# sensormoisture.net
KiCad netlist of a schematic drawn in EAGLE
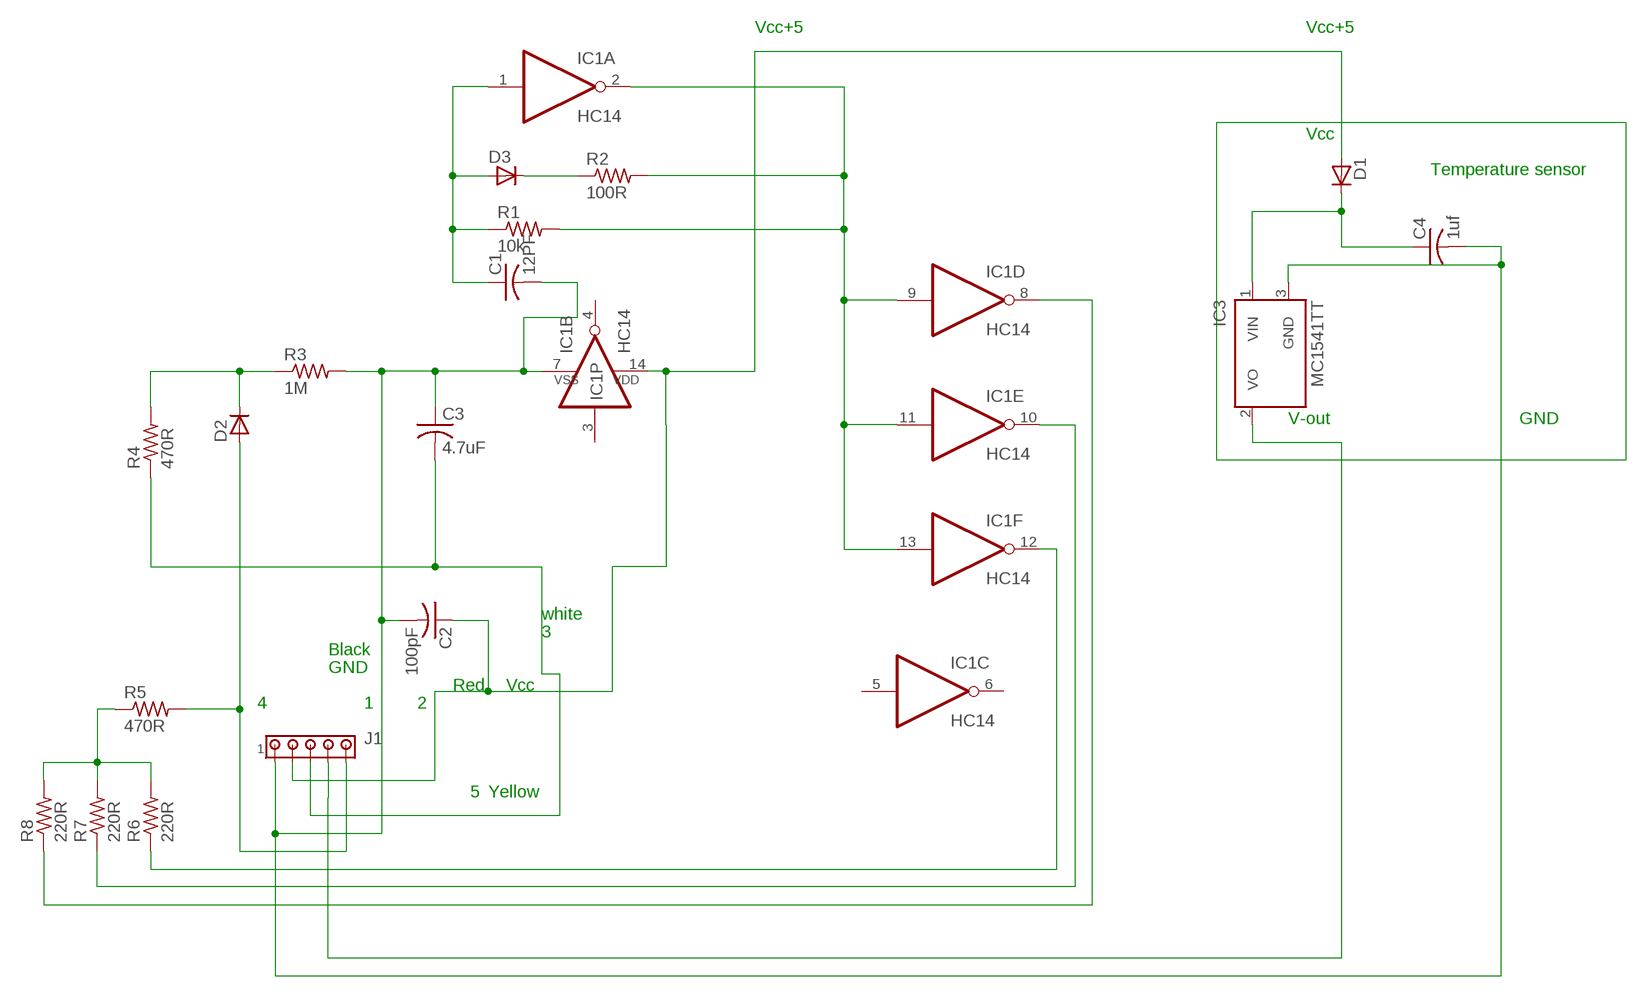
[diagram p0: schematic, sheet 1]

(export (version "E")
  (design (tool "Eeschema 10.0.6"))
  (components
    (comp (ref "C1")
      (value "12PF")
      (footprint "eagle-import:C0805")
      (libsource (lib "eagle-import") (part "C-USC0805"))
    )
    (comp (ref "C2")
      (value "100pF")
      (footprint "eagle-import:C1206K")
      (libsource (lib "eagle-import") (part "C-USC1206K"))
    )
    (comp (ref "C3")
      (value "4.7uF")
      (footprint "eagle-import:C1206")
      (libsource (lib "eagle-import") (part "C-USC1206"))
    )
    (comp (ref "C4")
      (value "1uf")
      (footprint "eagle-import:C1206K")
      (libsource (lib "eagle-import") (part "C-USC1206K"))
    )
    (comp (ref "D1")
      (value "D-MLL-34")
      (footprint "eagle-import:MELF-MLL34")
      (libsource (lib "eagle-import") (part "D-MLL-34"))
    )
    (comp (ref "D2")
      (value "D-MLL-34")
      (footprint "eagle-import:MELF-MLL34")
      (libsource (lib "eagle-import") (part "D-MLL-34"))
    )
    (comp (ref "D3")
      (value "D-MLL-34")
      (footprint "eagle-import:MELF-MLL34")
      (libsource (lib "eagle-import") (part "D-MLL-34"))
    )
    (comp (ref "IC1")
      (value "HC14")
      (footprint "eagle-import:SO14")
      (libsource (lib "eagle-import") (part "4584D"))
    )
    (comp (ref "IC3")
      (value "MC1541TT")
      (footprint "eagle-import:SOT23")
      (libsource (lib "eagle-import") (part "MC15TT41"))
    )
    (comp (ref "J1")
      (value "MTA05-100")
      (footprint "eagle-import:10X05MTA")
      (libsource (lib "eagle-import") (part "MTA05-100"))
    )
    (comp (ref "R1")
      (value "10k")
      (footprint "eagle-import:M0805")
      (libsource (lib "eagle-import") (part "R-US_M0805"))
    )
    (comp (ref "R2")
      (value "100R")
      (footprint "eagle-import:M0805")
      (libsource (lib "eagle-import") (part "R-US_M0805"))
    )
    (comp (ref "R3")
      (value "1M")
      (footprint "eagle-import:M0805")
      (libsource (lib "eagle-import") (part "R-US_M0805"))
    )
    (comp (ref "R4")
      (value "470R")
      (footprint "eagle-import:M0805")
      (libsource (lib "eagle-import") (part "R-US_M0805"))
    )
    (comp (ref "R5")
      (value "470R")
      (footprint "eagle-import:M0805")
      (libsource (lib "eagle-import") (part "R-US_M0805"))
    )
    (comp (ref "R6")
      (value "220R")
      (footprint "eagle-import:M0805")
      (libsource (lib "eagle-import") (part "R-US_M0805"))
    )
    (comp (ref "R7")
      (value "220R")
      (footprint "eagle-import:M0805")
      (libsource (lib "eagle-import") (part "R-US_M0805"))
    )
    (comp (ref "R8")
      (value "220R")
      (footprint "eagle-import:M0805")
      (libsource (lib "eagle-import") (part "R-US_M0805"))
    )
  )
  (nets
    (net (code "1") (name "Net-(C3-Pad2)") (class "Default")
      (node (ref "C3") (pin "2") (pinfunction "2_2") (pintype "passive"))
      (node (ref "J1") (pin "3") (pinfunction "3_3") (pintype "passive"))
      (node (ref "R4") (pin "1") (pinfunction "1_1") (pintype "passive"))
    )
    (net (code "2") (name "Net-(D1-A)") (class "Default")
      (node (ref "C2") (pin "1") (pinfunction "1_1") (pintype "passive"))
      (node (ref "D1") (pin "2") (pinfunction "A_2") (pintype "passive"))
      (node (ref "IC1") (pin "14") (pinfunction "VDD_14") (pintype "power_in"))
      (node (ref "J1") (pin "2") (pinfunction "2_2") (pintype "passive"))
    )
    (net (code "3") (name "Net-(D1-C)") (class "Default")
      (node (ref "C4") (pin "1") (pinfunction "1_1") (pintype "passive"))
      (node (ref "D1") (pin "1") (pinfunction "C_1") (pintype "passive"))
      (node (ref "IC3") (pin "1") (pinfunction "VIN_1") (pintype "input"))
    )
    (net (code "4") (name "Net-(D2-A)") (class "Default")
      (node (ref "D2") (pin "2") (pinfunction "A_2") (pintype "passive"))
      (node (ref "J1") (pin "5") (pinfunction "5_5") (pintype "passive"))
      (node (ref "R5") (pin "2") (pinfunction "2_2") (pintype "passive"))
    )
    (net (code "5") (name "Net-(D2-C)") (class "Default")
      (node (ref "D2") (pin "1") (pinfunction "C_1") (pintype "passive"))
      (node (ref "R3") (pin "1") (pinfunction "1_1") (pintype "passive"))
      (node (ref "R4") (pin "2") (pinfunction "2_2") (pintype "passive"))
    )
    (net (code "6") (name "Net-(D3-A)") (class "Default")
      (node (ref "C1") (pin "1") (pinfunction "1_1") (pintype "passive"))
      (node (ref "D3") (pin "2") (pinfunction "A_2") (pintype "passive"))
      (node (ref "IC1") (pin "1") (pinfunction "I_1") (pintype "input"))
      (node (ref "R1") (pin "1") (pinfunction "1_1") (pintype "passive"))
    )
    (net (code "7") (name "Net-(D3-C)") (class "Default")
      (node (ref "D3") (pin "1") (pinfunction "C_1") (pintype "passive"))
      (node (ref "R2") (pin "1") (pinfunction "1_1") (pintype "passive"))
    )
    (net (code "8") (name "Net-(IC1A-O)") (class "Default")
      (node (ref "IC1") (pin "11") (pinfunction "I_11") (pintype "input"))
      (node (ref "IC1") (pin "13") (pinfunction "I_13") (pintype "input"))
      (node (ref "IC1") (pin "2") (pinfunction "O_2") (pintype "output"))
      (node (ref "IC1") (pin "9") (pinfunction "I_9") (pintype "input"))
      (node (ref "R1") (pin "2") (pinfunction "2_2") (pintype "passive"))
      (node (ref "R2") (pin "2") (pinfunction "2_2") (pintype "passive"))
    )
    (net (code "9") (name "Net-(IC1D-O)") (class "Default")
      (node (ref "IC1") (pin "8") (pinfunction "O_8") (pintype "output"))
      (node (ref "R8") (pin "1") (pinfunction "1_1") (pintype "passive"))
    )
    (net (code "10") (name "Net-(IC1E-O)") (class "Default")
      (node (ref "IC1") (pin "10") (pinfunction "O_10") (pintype "output"))
      (node (ref "R7") (pin "1") (pinfunction "1_1") (pintype "passive"))
    )
    (net (code "11") (name "Net-(IC1F-O)") (class "Default")
      (node (ref "IC1") (pin "12") (pinfunction "O_12") (pintype "output"))
      (node (ref "R6") (pin "1") (pinfunction "1_1") (pintype "passive"))
    )
    (net (code "12") (name "Net-(IC1G-VSS)") (class "Default")
      (node (ref "C1") (pin "2") (pinfunction "2_2") (pintype "passive"))
      (node (ref "C2") (pin "2") (pinfunction "2_2") (pintype "passive"))
      (node (ref "C3") (pin "1") (pinfunction "1_1") (pintype "passive"))
      (node (ref "C4") (pin "2") (pinfunction "2_2") (pintype "passive"))
      (node (ref "IC1") (pin "7") (pinfunction "VSS_7") (pintype "power_in"))
      (node (ref "IC3") (pin "3") (pinfunction "GND_3") (pintype "passive"))
      (node (ref "J1") (pin "1") (pinfunction "1_1") (pintype "passive"))
      (node (ref "R3") (pin "2") (pinfunction "2_2") (pintype "passive"))
    )
    (net (code "13") (name "Net-(IC3-VO)") (class "Default")
      (node (ref "IC3") (pin "2") (pinfunction "VO_2") (pintype "output"))
      (node (ref "J1") (pin "4") (pinfunction "4_4") (pintype "passive"))
    )
    (net (code "14") (name "Net-(R5-Pad1)") (class "Default")
      (node (ref "R5") (pin "1") (pinfunction "1_1") (pintype "passive"))
      (node (ref "R6") (pin "2") (pinfunction "2_2") (pintype "passive"))
      (node (ref "R7") (pin "2") (pinfunction "2_2") (pintype "passive"))
      (node (ref "R8") (pin "2") (pinfunction "2_2") (pintype "passive"))
    )
    (net (code "15") (name "unconnected-(IC1B-I-Pad3)") (class "Default")
      (node (ref "IC1") (pin "3") (pinfunction "I_3") (pintype "input"))
    )
    (net (code "16") (name "unconnected-(IC1B-O-Pad4)") (class "Default")
      (node (ref "IC1") (pin "4") (pinfunction "O_4") (pintype "output"))
    )
    (net (code "17") (name "unconnected-(IC1C-I-Pad5)") (class "Default")
      (node (ref "IC1") (pin "5") (pinfunction "I_5") (pintype "input"))
    )
    (net (code "18") (name "unconnected-(IC1C-O-Pad6)") (class "Default")
      (node (ref "IC1") (pin "6") (pinfunction "O_6") (pintype "output"))
    )
  )
)
